# SCH_Reverse_Voltage_protection_2022-05-1.net
KiCad netlist of a schematic drawn in EasyEDA
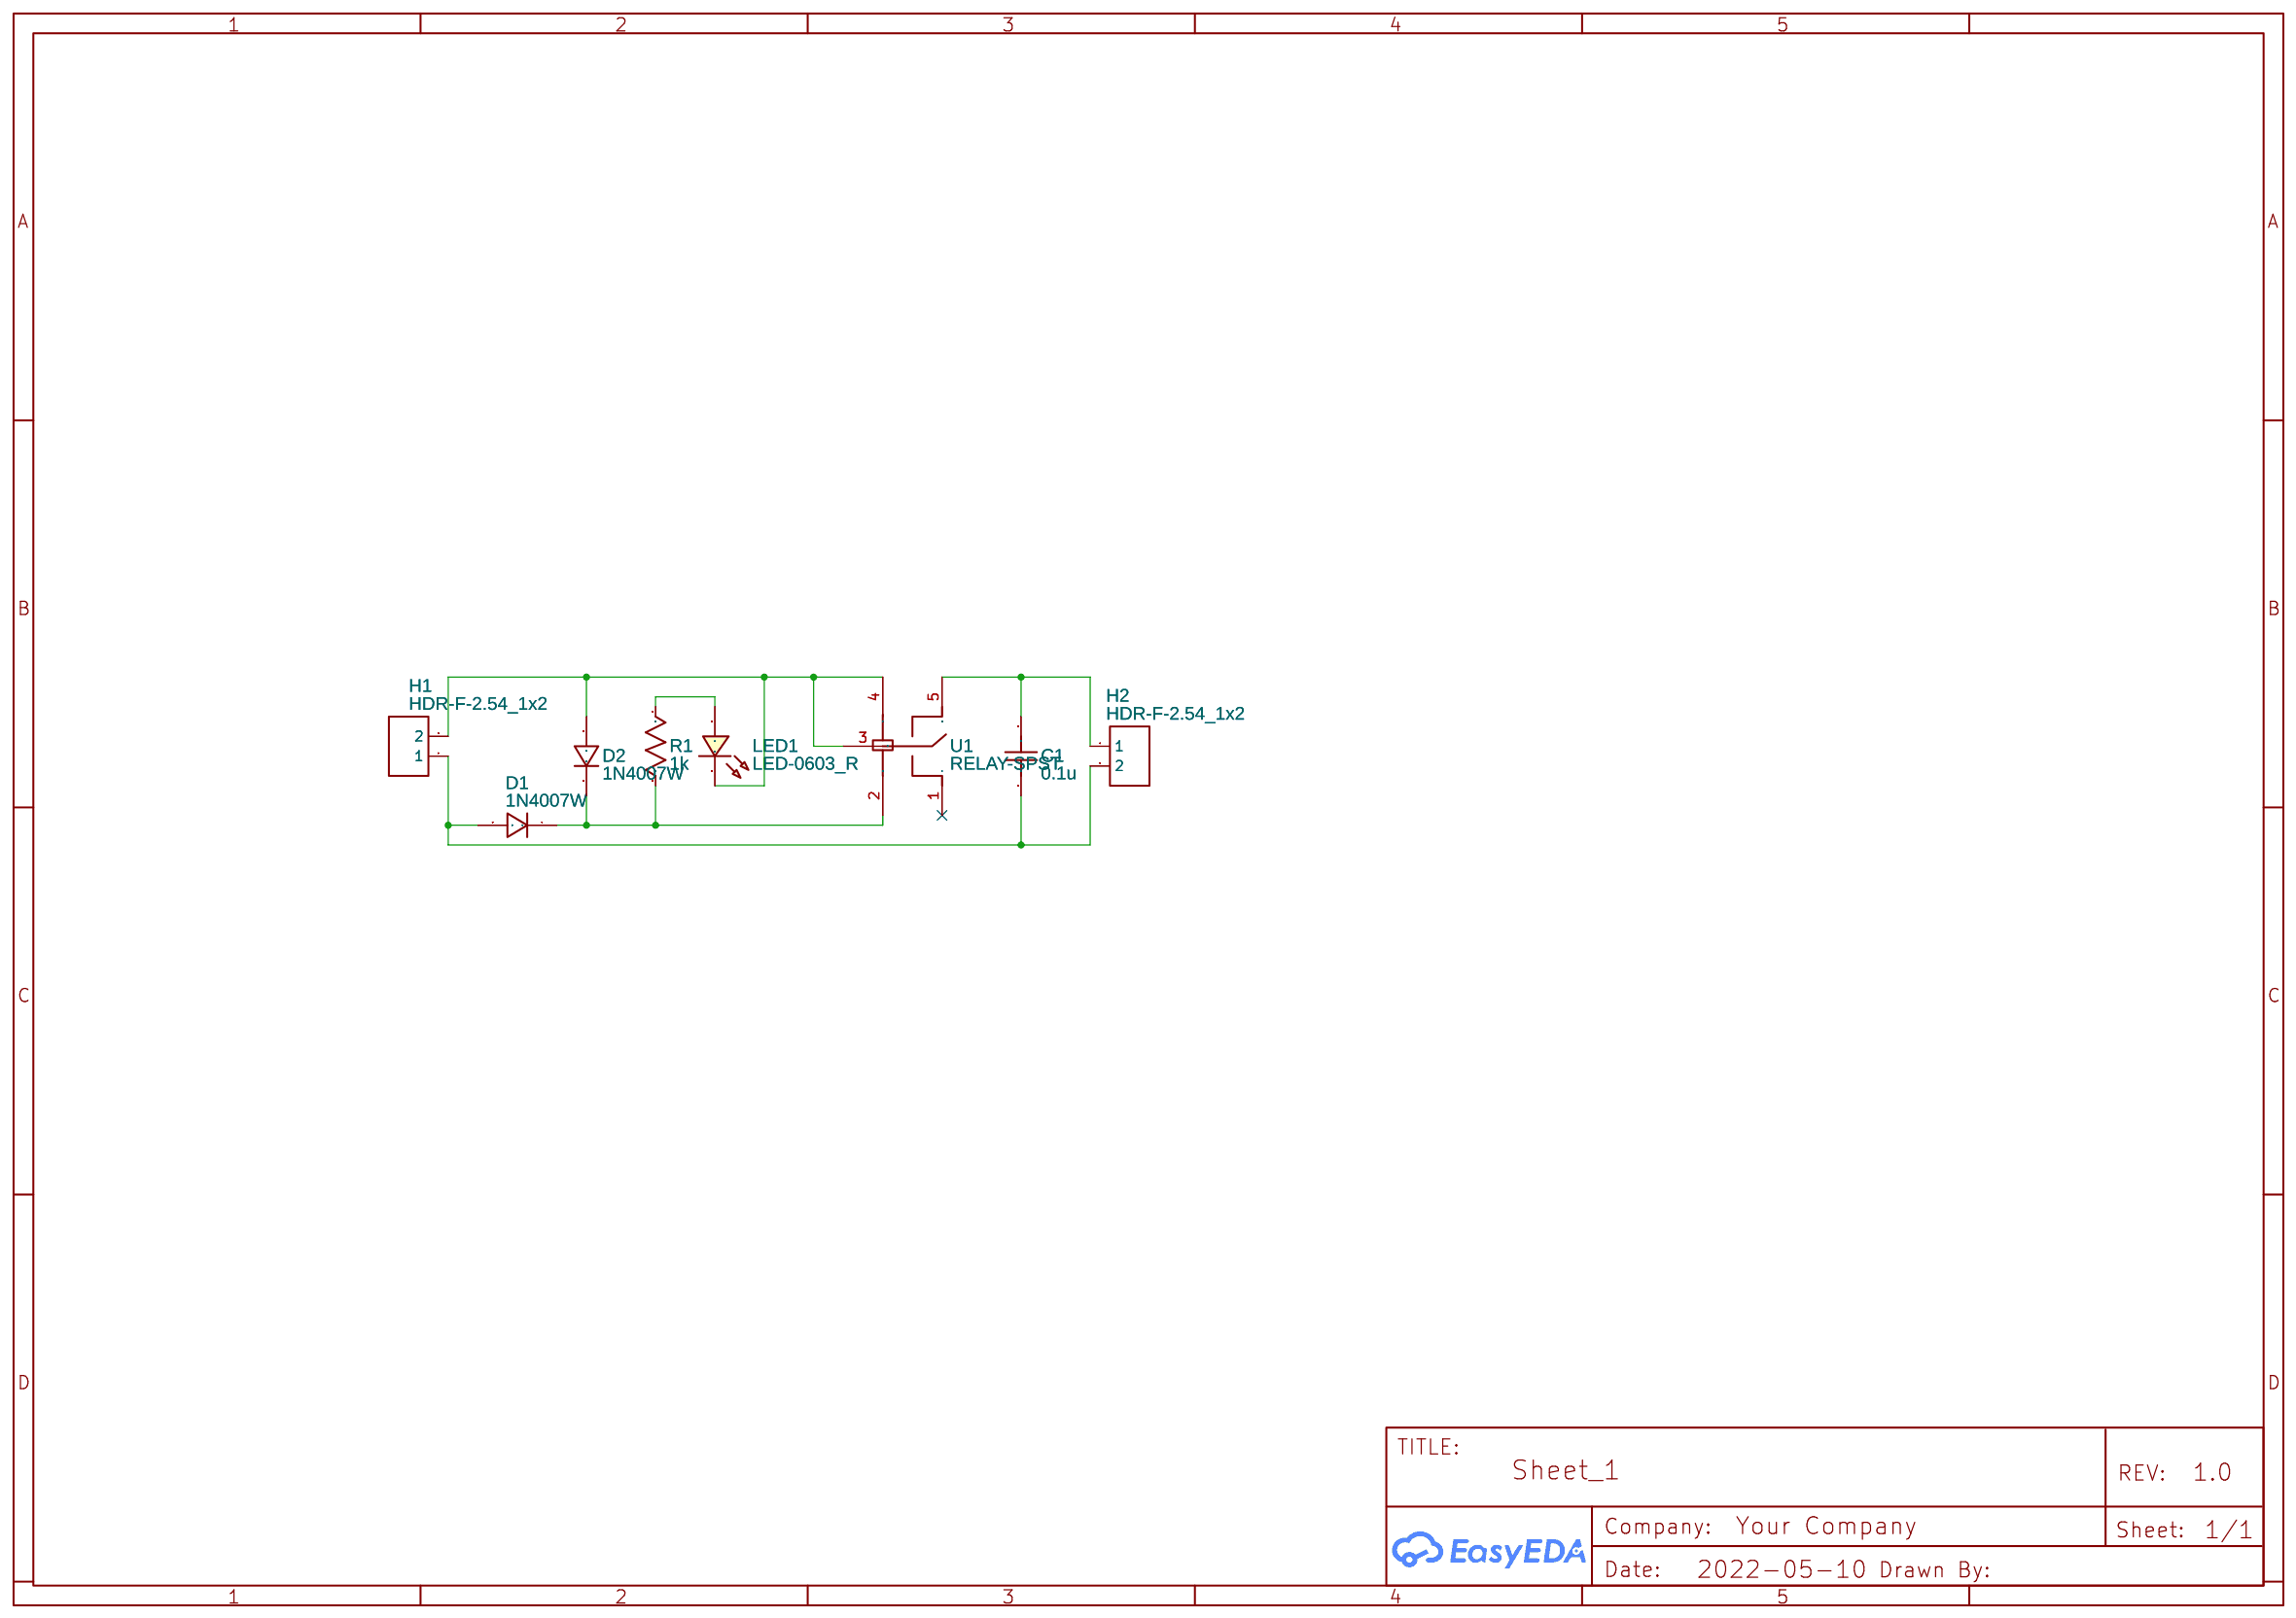
[diagram p0: schematic sheet]

(export (version "E")
  (design (tool "Eeschema 10.0.6"))
  (components
    (comp (ref "C1") (value "0.1u") (libsource (lib "") (part "C_0603_US")))
    (comp (ref "D1")
      (value "1N4007W")
      (fields (field (name "BOM_Supplier Part") "C328592"))
      (libsource (lib "") (part "1N4007W_1"))
    )
    (comp (ref "D2")
      (value "1N4007W")
      (fields (field (name "BOM_Supplier Part") "C328592"))
      (libsource (lib "") (part "1N4007W"))
    )
    (comp (ref "H1")
      (value "HDR-F-2.54_1x2")
      (fields (field (name "BOM_Supplier Part") "C49661"))
      (libsource (lib "") (part "HDR-F-2.54_1x2"))
    )
    (comp (ref "H2")
      (value "HDR-F-2.54_1x2")
      (fields (field (name "BOM_Supplier Part") "C49661"))
      (libsource (lib "") (part "HDR-F-2.54_1x2_1"))
    )
    (comp (ref "LED1")
      (value "LED-0603_R")
      (fields
        (field (name "BOM_Manufacturer Part") "19-217/R6C-AL1M2VY/3T")
        (field (name "BOM_Supplier Part") "C72044")
      )
      (libsource (lib "") (part "LED-0603_R"))
    )
    (comp (ref "R1") (value "1k") (libsource (lib "") (part "R_AXIAL-0.3_US")))
    (comp (ref "U1")
      (value "RELAY-SPST")
      (fields
        (field (name "BOM_Manufacturer Part") "Relay-SPST")
        (field (name "BOM_Supplier Part") "C2941249")
      )
      (libsource (lib "") (part "RELAY-SPST"))
    )
  )
  (nets
    (net (code "1") (name "Net-(C1-Pad1)") (class "Default")
      (node (ref "C1") (pin "1") (pinfunction "1_1") (pintype "unspecified"))
      (node (ref "D1") (pin "2") (pinfunction "2_2") (pintype "unspecified"))
      (node (ref "H1") (pin "1") (pinfunction "1_1") (pintype "input"))
      (node (ref "H2") (pin "2") (pinfunction "2_2") (pintype "input"))
    )
    (net (code "2") (name "Net-(C1-Pad2)") (class "Default")
      (node (ref "C1") (pin "2") (pinfunction "2_2") (pintype "unspecified"))
      (node (ref "H2") (pin "1") (pinfunction "1_1") (pintype "input"))
      (node (ref "U1") (pin "5") (pinfunction "5_5") (pintype "unspecified"))
    )
    (net (code "3") (name "Net-(D1-Pad1)") (class "Default")
      (node (ref "D1") (pin "1") (pinfunction "1_1") (pintype "unspecified"))
      (node (ref "D2") (pin "1") (pinfunction "1_1") (pintype "unspecified"))
      (node (ref "R1") (pin "2") (pinfunction "2_2") (pintype "unspecified"))
      (node (ref "U1") (pin "2") (pinfunction "2_2") (pintype "unspecified"))
    )
    (net (code "4") (name "Net-(D2-Pad2)") (class "Default")
      (node (ref "D2") (pin "2") (pinfunction "2_2") (pintype "unspecified"))
      (node (ref "H1") (pin "2") (pinfunction "2_2") (pintype "input"))
      (node (ref "LED1") (pin "2") (pinfunction "2_2") (pintype "unspecified"))
      (node (ref "U1") (pin "3") (pinfunction "3_3") (pintype "unspecified"))
      (node (ref "U1") (pin "4") (pinfunction "4_4") (pintype "unspecified"))
    )
    (net (code "5") (name "Net-(LED1-Pad1)") (class "Default")
      (node (ref "LED1") (pin "1") (pinfunction "1_1") (pintype "unspecified"))
      (node (ref "R1") (pin "1") (pinfunction "1_1") (pintype "unspecified"))
    )
    (net (code "6") (name "unconnected-(U1-Pad1)") (class "Default")
      (node (ref "U1") (pin "1") (pinfunction "1_1") (pintype "unspecified+no_connect"))
    )
  )
)
